# uSD_to_ICSP_v1.net
KiCad netlist of a schematic drawn in EAGLE
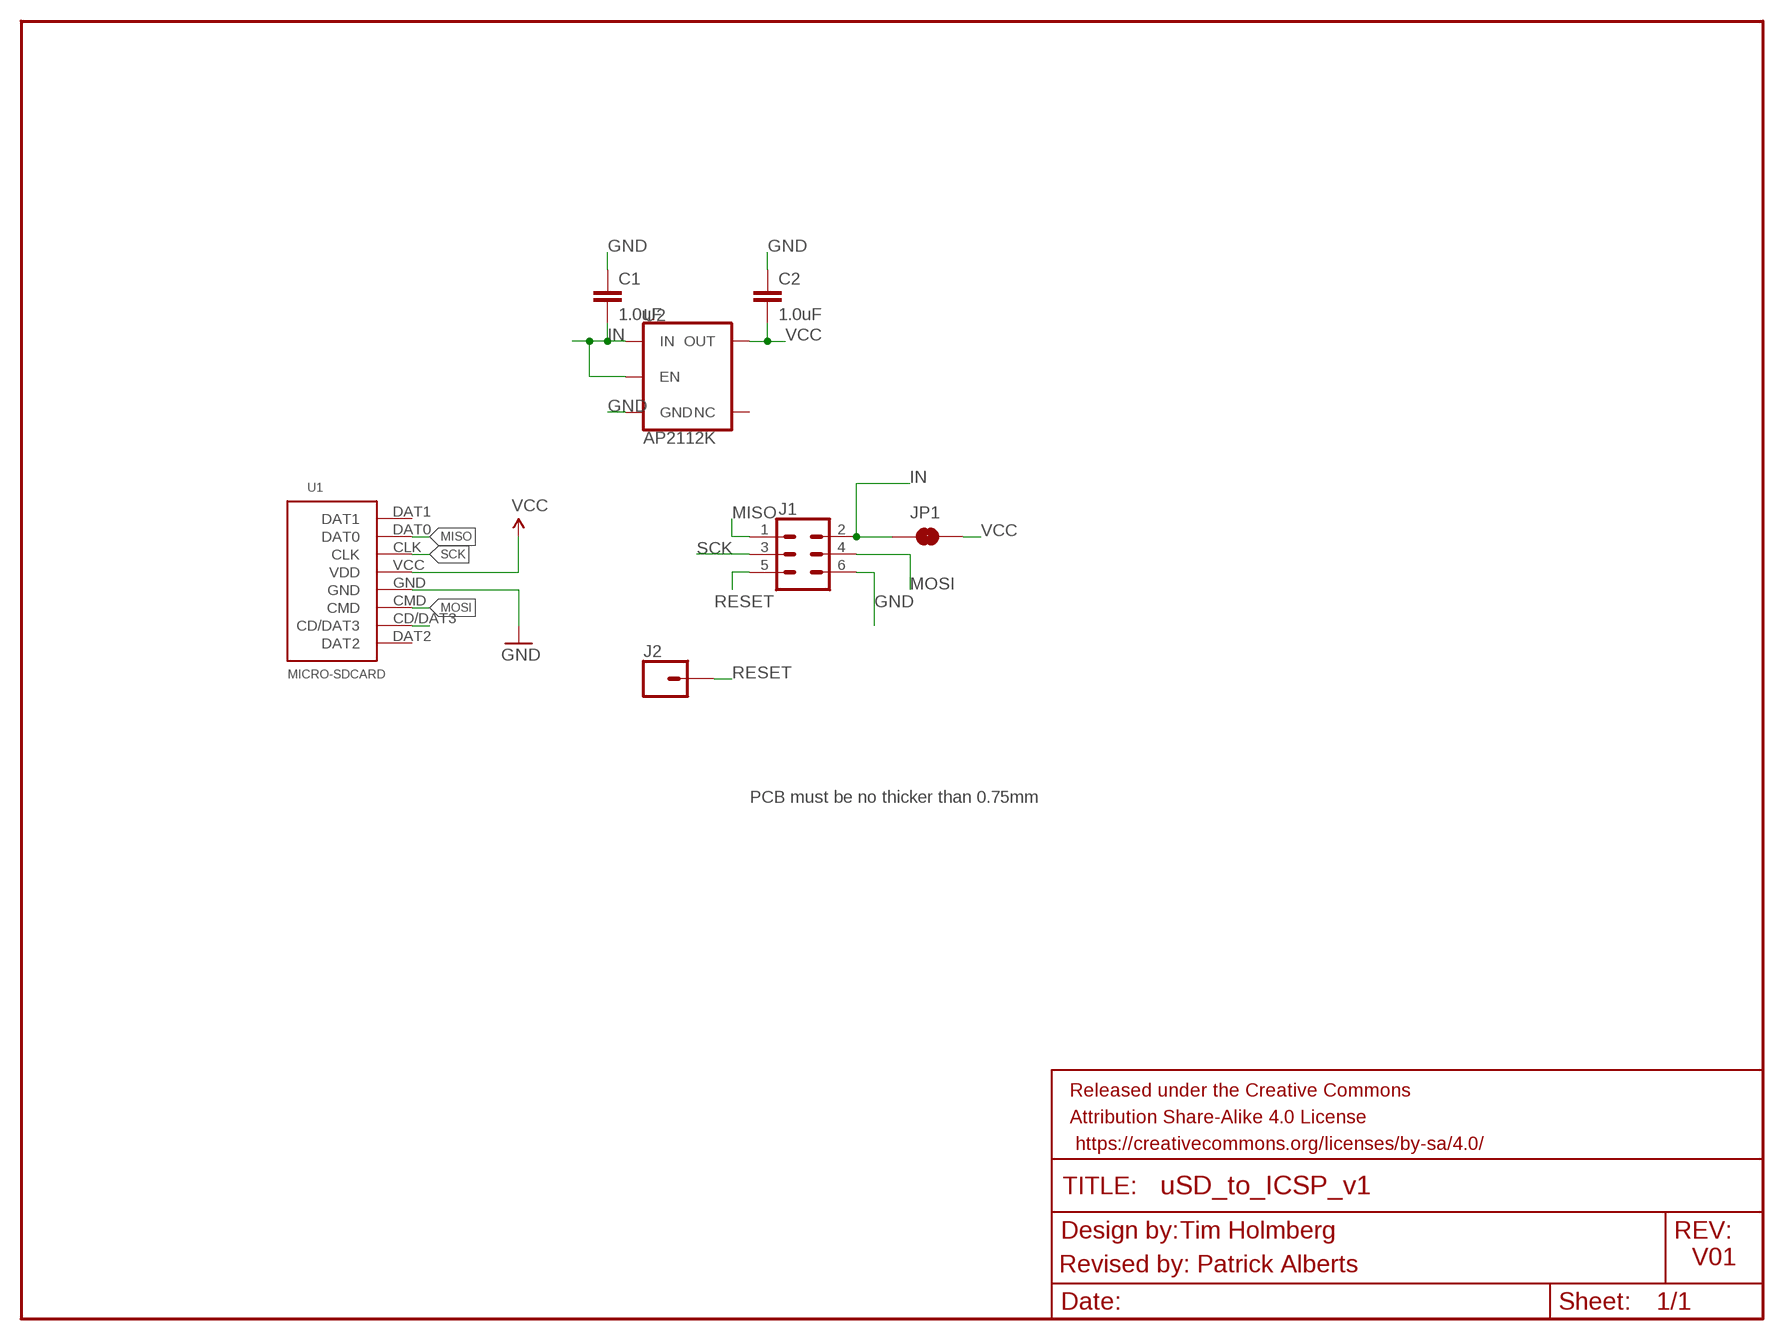
[diagram p0: schematic, sheet 1]

(export (version "E")
  (design (tool "Eeschema 10.0.6"))
  (components
    (comp (ref "C1")
      (value "1.0uF")
      (footprint "eagle-import:0805")
      (libsource (lib "eagle-import") (part "1.0UF-0805-25V-10%"))
    )
    (comp (ref "C2")
      (value "1.0uF")
      (footprint "eagle-import:0805")
      (libsource (lib "eagle-import") (part "1.0UF-0805-25V-10%"))
    )
    (comp (ref "FRAME1")
      (value "FRAME-LETTER")
      (footprint "eagle-import:CREATIVE_COMMONS")
      (fields (field (name "DESIGNER") "NAME"))
      (libsource (lib "eagle-import") (part "FRAME-LETTER"))
    )
    (comp (ref "J1")
      (value "CONN_03X2NO_SILK")
      (footprint "eagle-import:2X3-NS")
      (libsource (lib "eagle-import") (part "CONN_03X2NO_SILK"))
    )
    (comp (ref "J2")
      (value "CONN_01PTH_LONGPAD")
      (footprint "eagle-import:1X01_LONGPAD")
      (libsource (lib "eagle-import") (part "CONN_01PTH_LONGPAD"))
    )
    (comp (ref "JP1")
      (value "JUMPER-SMT_2_NC_TRACE_NO-SILK")
      (footprint "eagle-import:SMT-JUMPER_2_NC_TRACE_NO-SILK")
      (libsource (lib "eagle-import") (part "JUMPER-SMT_2_NC_TRACE_NO-SILK"))
    )
    (comp (ref "U1")
      (value "MICRO-SDCARD")
      (footprint "eagle-import:MICRO-SDCARD")
      (libsource (lib "eagle-import") (part "MICRO-SDCARD"))
    )
    (comp (ref "U2")
      (value "AP2112K")
      (footprint "eagle-import:SOT23-5")
      (libsource (lib "eagle-import") (part "V_REG_AP2112K-3.3V"))
    )
  )
  (nets
    (net (code "1") (name "/IN") (class "Default")
      (node (ref "C1") (pin "2") (pinfunction "2_2") (pintype "passive"))
      (node (ref "J1") (pin "2") (pinfunction "2_2") (pintype "bidirectional"))
      (node (ref "JP1") (pin "1") (pinfunction "1_1") (pintype "passive"))
      (node (ref "U2") (pin "1") (pinfunction "IN_1") (pintype "input"))
      (node (ref "U2") (pin "3") (pinfunction "EN_3") (pintype "input"))
    )
    (net (code "2") (name "/RESET") (class "Default")
      (node (ref "J1") (pin "5") (pinfunction "5_5") (pintype "bidirectional"))
      (node (ref "J2") (pin "1") (pinfunction "1_1") (pintype "passive"))
    )
    (net (code "3") (name "GND") (class "Default")
      (node (ref "C1") (pin "1") (pinfunction "1_1") (pintype "passive"))
      (node (ref "C2") (pin "1") (pinfunction "1_1") (pintype "passive"))
      (node (ref "J1") (pin "6") (pinfunction "6_6") (pintype "bidirectional"))
      (node (ref "U1") (pin "GND") (pinfunction "GND_GND") (pintype "bidirectional"))
      (node (ref "U2") (pin "2") (pinfunction "GND_2") (pintype "input"))
    )
    (net (code "4") (name "MISO") (class "Default")
      (node (ref "J1") (pin "1") (pinfunction "1_1") (pintype "bidirectional"))
      (node (ref "U1") (pin "DAT0") (pinfunction "DAT0_DAT0") (pintype "bidirectional"))
    )
    (net (code "5") (name "MOSI") (class "Default")
      (node (ref "J1") (pin "4") (pinfunction "4_4") (pintype "bidirectional"))
      (node (ref "U1") (pin "CMD") (pinfunction "CMD_CMD") (pintype "bidirectional"))
    )
    (net (code "6") (name "SCK") (class "Default")
      (node (ref "J1") (pin "3") (pinfunction "3_3") (pintype "bidirectional"))
      (node (ref "U1") (pin "CLK") (pinfunction "CLK_CLK") (pintype "bidirectional"))
    )
    (net (code "7") (name "VCC") (class "Default")
      (node (ref "C2") (pin "2") (pinfunction "2_2") (pintype "passive"))
      (node (ref "JP1") (pin "2") (pinfunction "2_2") (pintype "passive"))
      (node (ref "U1") (pin "VCC") (pinfunction "VDD_VCC") (pintype "bidirectional"))
      (node (ref "U2") (pin "5") (pinfunction "OUT_5") (pintype "passive"))
    )
    (net (code "8") (name "unconnected-(U1-PadCD{slash}DAT3)") (class "Default")
      (node (ref "U1") (pin "CD/DAT3") (pinfunction "CD/DAT3_CD/DAT3") (pintype "bidirectional"))
    )
    (net (code "9") (name "unconnected-(U1-PadDAT1)") (class "Default")
      (node (ref "U1") (pin "DAT1") (pinfunction "DAT1_DAT1") (pintype "bidirectional"))
    )
    (net (code "10") (name "unconnected-(U1-PadDAT2)") (class "Default")
      (node (ref "U1") (pin "DAT2") (pinfunction "DAT2_DAT2") (pintype "bidirectional"))
    )
    (net (code "11") (name "unconnected-(U2-NC-Pad4)") (class "Default")
      (node (ref "U2") (pin "4") (pinfunction "NC_4") (pintype "no_connect"))
    )
  )
)
